# fan_interface.net
KiCad netlist of a schematic drawn in Altium Designer
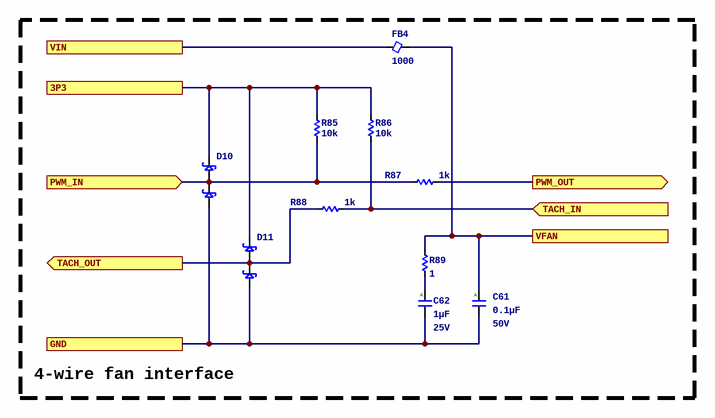
[diagram p0: fan_interface.SchDoc]

(export (version "E")
  (design (tool "Eeschema 10.0.6"))
  (components
    (comp (ref "C61")
      (value "CGA2B3X7R1H104M050BB")
      (footprint "C0402_0.55MM")
      (description "CAP CER 0.1UF 50V X7R 0402")
      (fields
        (field (name "CAPACITANCE") "0.1µF")
        (field (name "VOLTAGE - RATED") "50V")
        (field (name "TOLERANCE") "±20%")
        (field (name "MANUFACTURER") "TDK Corporation")
      )
      (libsource (lib "sscp") (part "__template_cap_auto"))
    )
    (comp (ref "C62")
      (value "CGJ3E1X7R1E105K080AC")
      (footprint "C0603_0.80MM")
      (description "CAP CER 1UF 25V X7R 0603")
      (fields
        (field (name "CAPACITANCE") "1µF")
        (field (name "VOLTAGE - RATED") "25V")
        (field (name "TOLERANCE") "±10%")
        (field (name "MANUFACTURER") "TDK Corporation")
      )
      (libsource (lib "sscp") (part "__template_cap_auto"))
    )
    (comp (ref "D10")
      (value "BAT54SLT1G")
      (footprint "3SOT23")
      (description "DIODE SCHOTTKY DUAL 30V SOT23")
      (fields (field (name "MANUFACTURER") "ON Semiconductor"))
      (libsource (lib "SSCP") (part "SCHOTTKY_30V_DUAL_BAT54SLT1G"))
    )
    (comp (ref "D11")
      (value "BAT54SLT1G")
      (footprint "3SOT23")
      (description "DIODE SCHOTTKY DUAL 30V SOT23")
      (fields (field (name "MANUFACTURER") "ON Semiconductor"))
      (libsource (lib "SSCP") (part "SCHOTTKY_30V_DUAL_BAT54SLT1G"))
    )
    (comp (ref "FB4")
      (value "MPZ2012S102AT000")
      (footprint "FB0805_1.05MM")
      (description "FERRITE BEAD 1 KOHM 0805 1LN")
      (fields
        (field (name "IMPEDANCE (OHMS @ 100MHZ)") "1000")
        (field (name "MANUFACTURER") "TDK Corporation")
      )
      (libsource (lib "sscp") (part "__template_ferrite"))
    )
    (comp (ref "R85")
      (value "~")
      (footprint "R0402_0.40MM")
      (description "RES SMD 10K OHM 1% 1/10W 0402")
      (fields (field (name "RESISTANCE") "10k") (field (name "TOLERANCE") "±1%"))
      (libsource (lib "sscp") (part "__template_resistor"))
    )
    (comp (ref "R86")
      (value "~")
      (footprint "R0402_0.40MM")
      (description "RES SMD 10K OHM 1% 1/10W 0402")
      (fields (field (name "RESISTANCE") "10k") (field (name "TOLERANCE") "±1%"))
      (libsource (lib "sscp") (part "__template_resistor"))
    )
    (comp (ref "R87")
      (value "~")
      (footprint "R0402_0.40MM")
      (description "RES SMD 1K OHM 1% 1/10W 0402")
      (fields (field (name "RESISTANCE") "1k") (field (name "TOLERANCE") "±1%"))
      (libsource (lib "sscp") (part "__template_resistor"))
    )
    (comp (ref "R88")
      (value "~")
      (footprint "R0402_0.40MM")
      (description "RES SMD 1K OHM 1% 1/10W 0402")
      (fields (field (name "RESISTANCE") "1k") (field (name "TOLERANCE") "±1%"))
      (libsource (lib "sscp") (part "__template_resistor"))
    )
    (comp (ref "R89")
      (value "ERJ-2BQF1R0X")
      (footprint "R0402_0.40MM")
      (description "RES SMD 1 OHM 1% 1/6W 0402")
      (fields
        (field (name "RESISTANCE") "1")
        (field (name "TOLERANCE") "±1%")
        (field (name "MANUFACTURER") "Panasonic Electronic Components")
      )
      (libsource (lib "sscp") (part "__template_resistor"))
    )
  )
  (nets
    (net (code "1") (name "/3P3") (class "Default")
      (node (ref "D10") (pin "2") (pintype "passive"))
      (node (ref "D11") (pin "2") (pintype "passive"))
      (node (ref "R85") (pin "1") (pintype "passive"))
      (node (ref "R86") (pin "1") (pintype "passive"))
    )
    (net (code "2") (name "/GND") (class "Default")
      (node (ref "C61") (pin "2") (pintype "passive"))
      (node (ref "C62") (pin "2") (pintype "passive"))
      (node (ref "D10") (pin "1") (pintype "passive"))
      (node (ref "D11") (pin "1") (pintype "passive"))
    )
    (net (code "3") (name "/PWM_IN") (class "Default")
      (node (ref "D10") (pin "3") (pintype "passive"))
      (node (ref "R85") (pin "2") (pintype "passive"))
      (node (ref "R87") (pin "2") (pintype "passive"))
    )
    (net (code "4") (name "/PWM_OUT") (class "Default") (node (ref "R87") (pin "1") (pintype "passive")))
    (net (code "5") (name "/TACH_IN") (class "Default")
      (node (ref "R86") (pin "2") (pintype "passive"))
      (node (ref "R88") (pin "1") (pintype "passive"))
    )
    (net (code "6") (name "/TACH_OUT") (class "Default")
      (node (ref "D11") (pin "3") (pintype "passive"))
      (node (ref "R88") (pin "2") (pintype "passive"))
    )
    (net (code "7") (name "/VFAN") (class "Default")
      (node (ref "C61") (pin "1") (pintype "passive"))
      (node (ref "FB4") (pin "2") (pintype "passive"))
      (node (ref "R89") (pin "2") (pintype "passive"))
    )
    (net (code "8") (name "/VIN") (class "Default") (node (ref "FB4") (pin "1") (pintype "passive")))
    (net (code "9") (name "Net-(C62-Pad1)") (class "Default")
      (node (ref "C62") (pin "1") (pintype "passive"))
      (node (ref "R89") (pin "1") (pintype "passive"))
    )
  )
)
